# DoorchimeCR2B.net
KiCad netlist of a schematic drawn in EAGLE
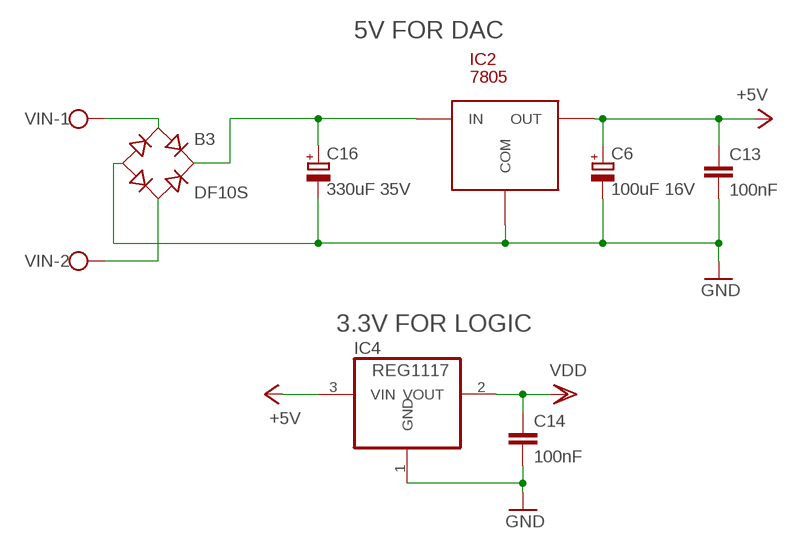
[diagram p0: schematic, sheet 1]
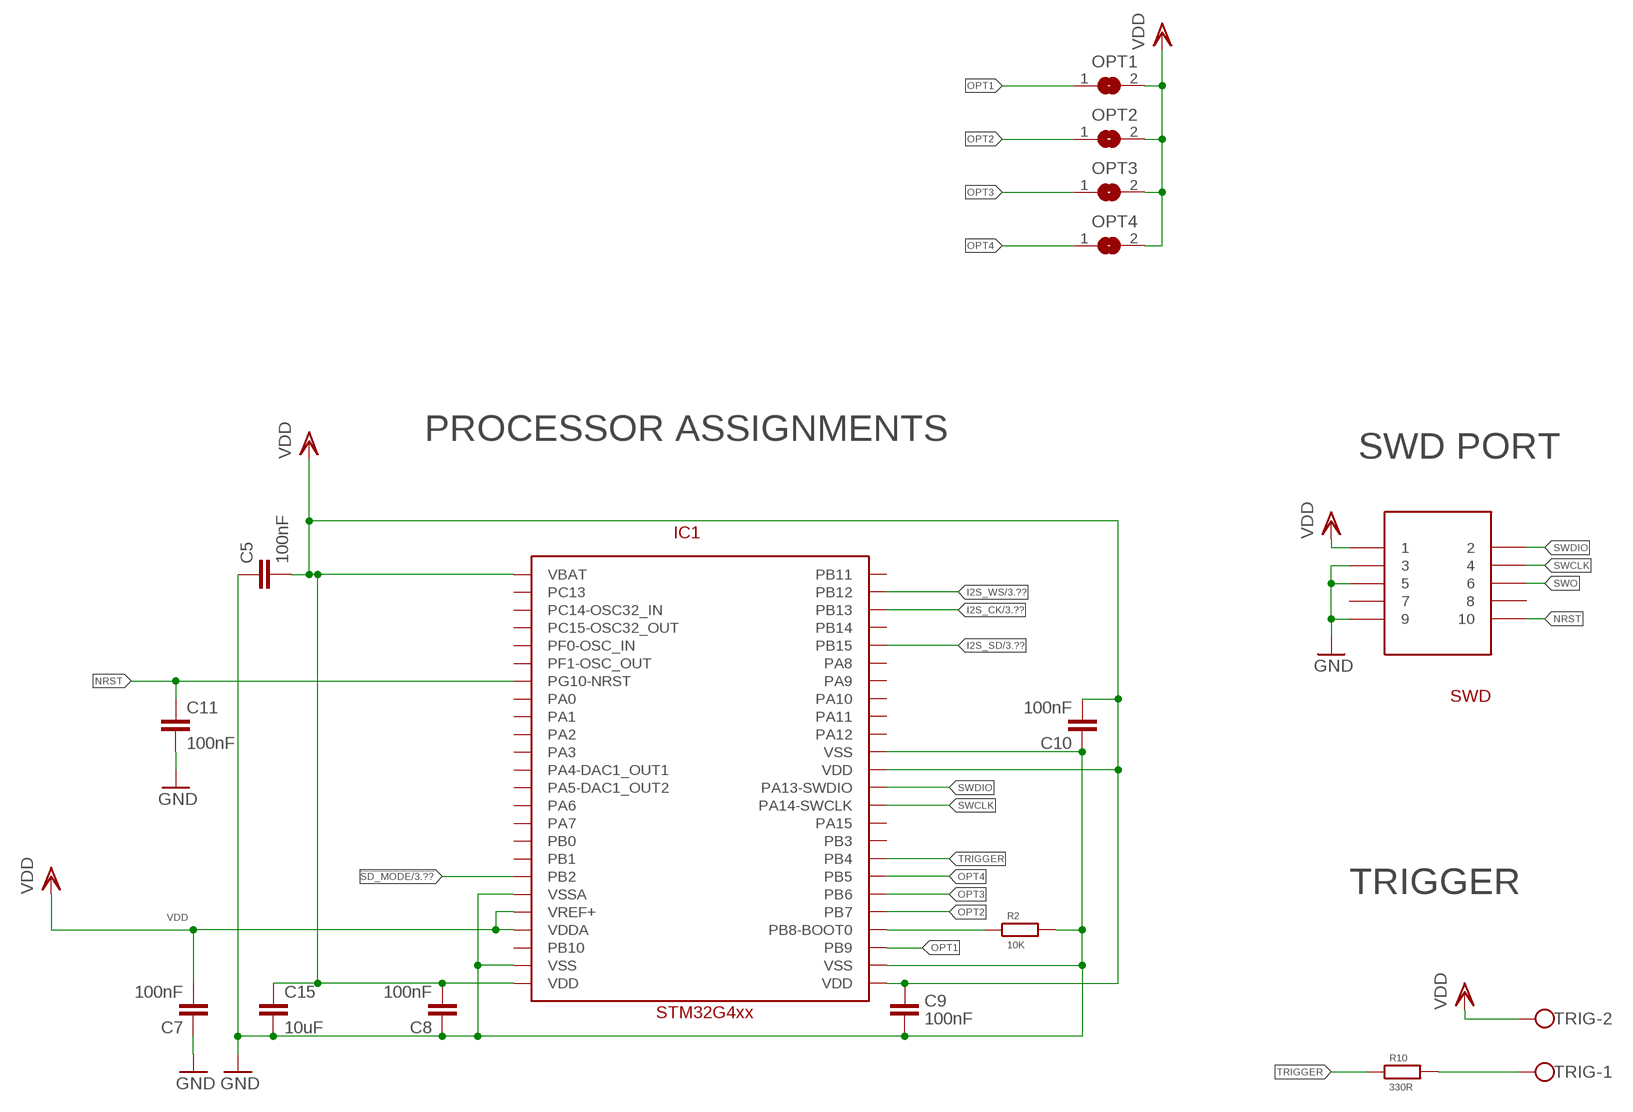
[diagram p1: schematic, sheet 2]
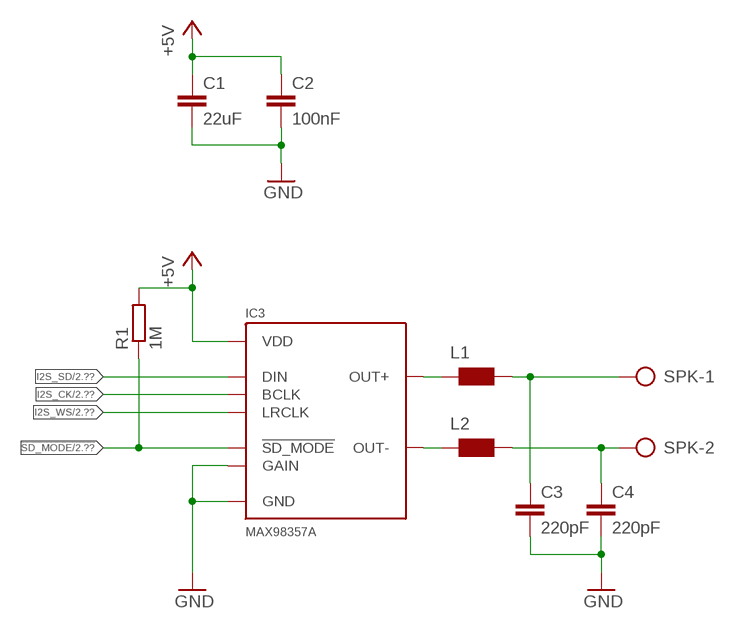
[diagram p2: schematic, sheet 3]

(export (version "E")
  (design (tool "Eeschema 10.0.6"))
  (components
    (comp (ref "B3")
      (value "DF10S")
      (footprint "eagle-import:DFS")
      (libsource (lib "eagle-import") (part "DFS10"))
    )
    (comp (ref "C6")
      (value "100uF 16V")
      (footprint "eagle-import:153CLV-0605")
      (libsource (lib "eagle-import") (part "CPOL-EU153CLV-0605"))
    )
    (comp (ref "C13")
      (value "100nF")
      (footprint "eagle-import:C0603")
      (libsource (lib "eagle-import") (part "C-EUC0603"))
    )
    (comp (ref "C14")
      (value "100nF")
      (footprint "eagle-import:C0603")
      (libsource (lib "eagle-import") (part "C-EUC0603"))
    )
    (comp (ref "C16")
      (value "330uF 35V")
      (footprint "eagle-import:153CLV-0807")
      (libsource (lib "eagle-import") (part "CPOL-EU153CLV-0807"))
    )
    (comp (ref "IC2")
      (value "7805")
      (footprint "eagle-import:D2PAK")
      (libsource (lib "eagle-import") (part "78XX-D2PAK"))
    )
    (comp (ref "IC4")
      (value "REG1117")
      (footprint "eagle-import:SOT223")
      (libsource (lib "eagle-import") (part "REG1117"))
    )
    (comp (ref "VIN")
      (value "W237-102")
      (footprint "eagle-import:W237-102")
      (fields (field (name "MPN") "237-102"))
      (libsource (lib "eagle-import") (part "W237-102"))
    )
    (comp (ref "C1")
      (value "22uF")
      (footprint "eagle-import:C0603")
      (libsource (lib "eagle-import") (part "C-EUC0603"))
    )
    (comp (ref "C2")
      (value "100nF")
      (footprint "eagle-import:C0603")
      (libsource (lib "eagle-import") (part "C-EUC0603"))
    )
    (comp (ref "C3")
      (value "220pF")
      (footprint "eagle-import:C0603")
      (libsource (lib "eagle-import") (part "C-EUC0603"))
    )
    (comp (ref "C4")
      (value "220pF")
      (footprint "eagle-import:C0603")
      (libsource (lib "eagle-import") (part "C-EUC0603"))
    )
    (comp (ref "IC3")
      (value "MAX98357A")
      (footprint "eagle-import:TQFN-16")
      (libsource (lib "eagle-import") (part "MAX98357A"))
    )
    (comp (ref "L1")
      (value "WE-CBF_0603")
      (footprint "eagle-import:0603")
      (libsource (lib "eagle-import") (part "WE-CBF_0603"))
    )
    (comp (ref "L2")
      (value "WE-CBF_0603")
      (footprint "eagle-import:0603")
      (libsource (lib "eagle-import") (part "WE-CBF_0603"))
    )
    (comp (ref "R1")
      (value "1M")
      (footprint "eagle-import:R0603")
      (libsource (lib "eagle-import") (part "R-EU_R0603"))
    )
    (comp (ref "SPK")
      (value "W237-102")
      (footprint "eagle-import:W237-102")
      (fields (field (name "MPN") "237-102"))
      (libsource (lib "eagle-import") (part "W237-102"))
    )
    (comp (ref "C5")
      (value "100nF")
      (footprint "eagle-import:C0603")
      (libsource (lib "eagle-import") (part "C-EUC0603"))
    )
    (comp (ref "C7")
      (value "100nF")
      (footprint "eagle-import:C0603")
      (libsource (lib "eagle-import") (part "C-EUC0603"))
    )
    (comp (ref "C8")
      (value "100nF")
      (footprint "eagle-import:C0603")
      (libsource (lib "eagle-import") (part "C-EUC0603"))
    )
    (comp (ref "C9")
      (value "100nF")
      (footprint "eagle-import:C0603")
      (libsource (lib "eagle-import") (part "C-EUC0603"))
    )
    (comp (ref "C10")
      (value "100nF")
      (footprint "eagle-import:C0603")
      (libsource (lib "eagle-import") (part "C-EUC0603"))
    )
    (comp (ref "C11")
      (value "100nF")
      (footprint "eagle-import:C0603")
      (libsource (lib "eagle-import") (part "C-EUC0603"))
    )
    (comp (ref "C15")
      (value "10uF")
      (footprint "eagle-import:C0603")
      (libsource (lib "eagle-import") (part "C-EUC0603"))
    )
    (comp (ref "IC1")
      (value "STM32G4xx")
      (footprint "eagle-import:TQFP48")
      (libsource (lib "eagle-import") (part "STM32G431-C8T6"))
    )
    (comp (ref "OPT1")
      (value "SJ")
      (footprint "eagle-import:SJ")
      (libsource (lib "eagle-import") (part "SJ"))
    )
    (comp (ref "OPT2")
      (value "SJ")
      (footprint "eagle-import:SJ")
      (libsource (lib "eagle-import") (part "SJ"))
    )
    (comp (ref "OPT3")
      (value "SJ")
      (footprint "eagle-import:SJ")
      (libsource (lib "eagle-import") (part "SJ"))
    )
    (comp (ref "OPT4")
      (value "SJ")
      (footprint "eagle-import:SJ")
      (libsource (lib "eagle-import") (part "SJ"))
    )
    (comp (ref "R2")
      (value "10K")
      (footprint "eagle-import:R0603")
      (libsource (lib "eagle-import") (part "R-EU_R0603"))
    )
    (comp (ref "R10")
      (value "330R")
      (footprint "eagle-import:R0603")
      (libsource (lib "eagle-import") (part "R-EU_R0603"))
    )
    (comp (ref "SWD")
      (value "FTSH-105-01")
      (footprint "eagle-import:FTSH-105-01-XXX-DV-K")
      (libsource (lib "eagle-import") (part "FTSH-105-01"))
    )
    (comp (ref "TRIG")
      (value "W237-102")
      (footprint "eagle-import:W237-102")
      (fields (field (name "MPN") "237-102"))
      (libsource (lib "eagle-import") (part "W237-102"))
    )
  )
  (nets
    (net (code "1") (name "+5V") (class "Default")
      (node (ref "C1") (pin "1") (pinfunction "1_1") (pintype "passive"))
      (node (ref "C13") (pin "1") (pinfunction "1_1") (pintype "passive"))
      (node (ref "C2") (pin "1") (pinfunction "1_1") (pintype "passive"))
      (node (ref "C6") (pin "+") (pinfunction "+_+") (pintype "passive"))
      (node (ref "IC2") (pin "OUT") (pinfunction "OUT_OUT") (pintype "bidirectional"))
      (node (ref "IC3") (pin "P$7") (pinfunction "VDD_P$7") (pintype "bidirectional"))
      (node (ref "IC3") (pin "P$8") (pinfunction "VDD_P$8") (pintype "bidirectional"))
      (node (ref "IC4") (pin "3") (pinfunction "VIN_3") (pintype "input"))
      (node (ref "R1") (pin "2") (pinfunction "2_2") (pintype "passive"))
    )
    (net (code "2") (name "GND") (class "Default")
      (node (ref "B3") (pin "-") (pinfunction "-_-") (pintype "passive"))
      (node (ref "C1") (pin "2") (pinfunction "2_2") (pintype "passive"))
      (node (ref "C10") (pin "1") (pinfunction "1_1") (pintype "passive"))
      (node (ref "C11") (pin "2") (pinfunction "2_2") (pintype "passive"))
      (node (ref "C13") (pin "2") (pinfunction "2_2") (pintype "passive"))
      (node (ref "C14") (pin "2") (pinfunction "2_2") (pintype "passive"))
      (node (ref "C15") (pin "2") (pinfunction "2_2") (pintype "passive"))
      (node (ref "C16") (pin "-") (pinfunction "-_-") (pintype "passive"))
      (node (ref "C2") (pin "2") (pinfunction "2_2") (pintype "passive"))
      (node (ref "C3") (pin "2") (pinfunction "2_2") (pintype "passive"))
      (node (ref "C4") (pin "2") (pinfunction "2_2") (pintype "passive"))
      (node (ref "C5") (pin "1") (pinfunction "1_1") (pintype "passive"))
      (node (ref "C6") (pin "-") (pinfunction "-_-") (pintype "passive"))
      (node (ref "C7") (pin "1") (pinfunction "1_1") (pintype "passive"))
      (node (ref "C8") (pin "1") (pinfunction "1_1") (pintype "passive"))
      (node (ref "C9") (pin "1") (pinfunction "1_1") (pintype "passive"))
      (node (ref "IC1") (pin "VSS@23") (pinfunction "VSS_VSS@23") (pintype "power_in"))
      (node (ref "IC1") (pin "VSS@35") (pinfunction "VSS_VSS@35") (pintype "power_in"))
      (node (ref "IC1") (pin "VSS@47") (pinfunction "VSS_VSS@47") (pintype "power_in"))
      (node (ref "IC1") (pin "VSSA") (pinfunction "VSSA_VSSA") (pintype "power_in"))
      (node (ref "IC2") (pin "COM") (pinfunction "COM_COM") (pintype "bidirectional"))
      (node (ref "IC3") (pin "P$11") (pinfunction "GND_P$11") (pintype "bidirectional"))
      (node (ref "IC3") (pin "P$15") (pinfunction "GND_P$15") (pintype "bidirectional"))
      (node (ref "IC3") (pin "P$2") (pinfunction "GAIN_P$2") (pintype "bidirectional"))
      (node (ref "IC3") (pin "P$3") (pinfunction "GND_P$3") (pintype "bidirectional"))
      (node (ref "IC3") (pin "P$EP") (pinfunction "GND_P$EP") (pintype "bidirectional"))
      (node (ref "IC4") (pin "1") (pinfunction "GND_1") (pintype "power_in"))
      (node (ref "R2") (pin "2") (pinfunction "2_2") (pintype "passive"))
      (node (ref "SWD") (pin "3") (pinfunction "3_3") (pintype "passive"))
      (node (ref "SWD") (pin "5") (pinfunction "5_5") (pintype "passive"))
      (node (ref "SWD") (pin "9") (pinfunction "9_9") (pintype "passive"))
    )
    (net (code "3") (name "I2S_CK") (class "Default")
      (node (ref "IC1") (pin "PB13") (pinfunction "PB13_PB13") (pintype "bidirectional"))
      (node (ref "IC3") (pin "P$16") (pinfunction "BCLK_P$16") (pintype "bidirectional"))
    )
    (net (code "4") (name "I2S_SD") (class "Default")
      (node (ref "IC1") (pin "PB15") (pinfunction "PB15_PB15") (pintype "bidirectional"))
      (node (ref "IC3") (pin "P$1") (pinfunction "DIN_P$1") (pintype "bidirectional"))
    )
    (net (code "5") (name "I2S_WS") (class "Default")
      (node (ref "IC1") (pin "PB12") (pinfunction "PB12_PB12") (pintype "bidirectional"))
      (node (ref "IC3") (pin "P$14") (pinfunction "LRCLK_P$14") (pintype "bidirectional"))
    )
    (net (code "6") (name "NRST") (class "Default")
      (node (ref "C11") (pin "1") (pinfunction "1_1") (pintype "passive"))
      (node (ref "IC1") (pin "PG10-NRST") (pinfunction "PG10-NRST_PG10-NRST") (pintype "bidirectional"))
      (node (ref "SWD") (pin "10") (pinfunction "10_10") (pintype "passive"))
    )
    (net (code "7") (name "Net-(B3-Pad+)") (class "Default")
      (node (ref "B3") (pin "+") (pinfunction "+_+") (pintype "passive"))
      (node (ref "C16") (pin "+") (pinfunction "+_+") (pintype "passive"))
      (node (ref "IC2") (pin "IN") (pinfunction "IN_IN") (pintype "bidirectional"))
    )
    (net (code "8") (name "Net-(IC1-PadPB8-BOOT0)") (class "Default")
      (node (ref "IC1") (pin "PB8-BOOT0") (pinfunction "PB8-BOOT0_PB8-BOOT0") (pintype "bidirectional"))
      (node (ref "R2") (pin "1") (pinfunction "1_1") (pintype "passive"))
    )
    (net (code "9") (name "Net-(IC3-OUT+)") (class "Default")
      (node (ref "IC3") (pin "P$9") (pinfunction "OUT+_P$9") (pintype "bidirectional"))
      (node (ref "L1") (pin "1") (pinfunction "1_1") (pintype "passive"))
    )
    (net (code "10") (name "Net-(IC3-OUT-)") (class "Default")
      (node (ref "IC3") (pin "P$10") (pinfunction "OUT-_P$10") (pintype "bidirectional"))
      (node (ref "L2") (pin "1") (pinfunction "1_1") (pintype "passive"))
    )
    (net (code "11") (name "Net-(SPKA-KL)") (class "Default")
      (node (ref "C3") (pin "1") (pinfunction "1_1") (pintype "passive"))
      (node (ref "L1") (pin "2") (pinfunction "2_2") (pintype "passive"))
      (node (ref "SPK") (pin "1") (pinfunction "KL_1") (pintype "passive"))
    )
    (net (code "12") (name "Net-(SPKB-KL)") (class "Default")
      (node (ref "C4") (pin "1") (pinfunction "1_1") (pintype "passive"))
      (node (ref "L2") (pin "2") (pinfunction "2_2") (pintype "passive"))
      (node (ref "SPK") (pin "2") (pinfunction "KL_2") (pintype "passive"))
    )
    (net (code "13") (name "Net-(TRIGA-KL)") (class "Default")
      (node (ref "R10") (pin "2") (pinfunction "2_2") (pintype "passive"))
      (node (ref "TRIG") (pin "1") (pinfunction "KL_1") (pintype "passive"))
    )
    (net (code "14") (name "Net-(VINA-KL)") (class "Default")
      (node (ref "B3") (pin "AC1") (pinfunction "AC1_AC1") (pintype "passive"))
      (node (ref "VIN") (pin "1") (pinfunction "KL_1") (pintype "passive"))
    )
    (net (code "15") (name "Net-(VINB-KL)") (class "Default")
      (node (ref "B3") (pin "AC2") (pinfunction "AC2_AC2") (pintype "passive"))
      (node (ref "VIN") (pin "2") (pinfunction "KL_2") (pintype "passive"))
    )
    (net (code "16") (name "OPT1") (class "Default")
      (node (ref "IC1") (pin "PB9") (pinfunction "PB9_PB9") (pintype "bidirectional"))
      (node (ref "OPT1") (pin "1") (pinfunction "1_1") (pintype "passive"))
    )
    (net (code "17") (name "OPT2") (class "Default")
      (node (ref "IC1") (pin "PB7") (pinfunction "PB7_PB7") (pintype "bidirectional"))
      (node (ref "OPT2") (pin "1") (pinfunction "1_1") (pintype "passive"))
    )
    (net (code "18") (name "OPT3") (class "Default")
      (node (ref "IC1") (pin "PB6") (pinfunction "PB6_PB6") (pintype "bidirectional"))
      (node (ref "OPT3") (pin "1") (pinfunction "1_1") (pintype "passive"))
    )
    (net (code "19") (name "OPT4") (class "Default")
      (node (ref "IC1") (pin "PB5") (pinfunction "PB5_PB5") (pintype "bidirectional"))
      (node (ref "OPT4") (pin "1") (pinfunction "1_1") (pintype "passive"))
    )
    (net (code "20") (name "SWCLK") (class "Default")
      (node (ref "IC1") (pin "PA14-SWCLK") (pinfunction "PA14-SWCLK_PA14-SWCLK") (pintype "bidirectional"))
      (node (ref "SWD") (pin "4") (pinfunction "4_4") (pintype "passive"))
    )
    (net (code "21") (name "SWDIO") (class "Default")
      (node (ref "IC1") (pin "PA13-SWDIO") (pinfunction "PA13-SWDIO_PA13-SWDIO") (pintype "bidirectional"))
      (node (ref "SWD") (pin "2") (pinfunction "2_2") (pintype "passive"))
    )
    (net (code "22") (name "SWO") (class "Default")
      (node (ref "SWD") (pin "6") (pinfunction "6_6") (pintype "passive"))
    )
    (net (code "23") (name "TRIGGER") (class "Default")
      (node (ref "IC1") (pin "PB4") (pinfunction "PB4_PB4") (pintype "bidirectional"))
      (node (ref "R10") (pin "1") (pinfunction "1_1") (pintype "passive"))
    )
    (net (code "24") (name "VDD") (class "Default")
      (node (ref "C10") (pin "2") (pinfunction "2_2") (pintype "passive"))
      (node (ref "C14") (pin "1") (pinfunction "1_1") (pintype "passive"))
      (node (ref "C15") (pin "1") (pinfunction "1_1") (pintype "passive"))
      (node (ref "C5") (pin "2") (pinfunction "2_2") (pintype "passive"))
      (node (ref "C7") (pin "2") (pinfunction "2_2") (pintype "passive"))
      (node (ref "C8") (pin "2") (pinfunction "2_2") (pintype "passive"))
      (node (ref "C9") (pin "2") (pinfunction "2_2") (pintype "passive"))
      (node (ref "IC1") (pin "VBAT") (pinfunction "VBAT_VBAT") (pintype "power_in"))
      (node (ref "IC1") (pin "VDD@24") (pinfunction "VDD_VDD@24") (pintype "power_in"))
      (node (ref "IC1") (pin "VDD@36") (pinfunction "VDD_VDD@36") (pintype "power_in"))
      (node (ref "IC1") (pin "VDD@48") (pinfunction "VDD_VDD@48") (pintype "power_in"))
      (node (ref "IC1") (pin "VDDA") (pinfunction "VDDA_VDDA") (pintype "power_in"))
      (node (ref "IC1") (pin "VREF+") (pinfunction "VREF+_VREF+") (pintype "power_in"))
      (node (ref "IC4") (pin "2") (pinfunction "VOUT_2") (pintype "output"))
      (node (ref "OPT1") (pin "2") (pinfunction "2_2") (pintype "passive"))
      (node (ref "OPT2") (pin "2") (pinfunction "2_2") (pintype "passive"))
      (node (ref "OPT3") (pin "2") (pinfunction "2_2") (pintype "passive"))
      (node (ref "OPT4") (pin "2") (pinfunction "2_2") (pintype "passive"))
      (node (ref "SWD") (pin "1") (pinfunction "1_1") (pintype "passive"))
      (node (ref "TRIG") (pin "2") (pinfunction "KL_2") (pintype "passive"))
    )
    (net (code "25") (name "unconnected-(IC1-PadPA0)") (class "Default")
      (node (ref "IC1") (pin "PA0") (pinfunction "PA0_PA0") (pintype "bidirectional"))
    )
    (net (code "26") (name "unconnected-(IC1-PadPA1)") (class "Default")
      (node (ref "IC1") (pin "PA1") (pinfunction "PA1_PA1") (pintype "bidirectional"))
    )
    (net (code "27") (name "unconnected-(IC1-PadPA2)") (class "Default")
      (node (ref "IC1") (pin "PA2") (pinfunction "PA2_PA2") (pintype "bidirectional"))
    )
    (net (code "28") (name "unconnected-(IC1-PadPA3)") (class "Default")
      (node (ref "IC1") (pin "PA3") (pinfunction "PA3_PA3") (pintype "bidirectional"))
    )
    (net (code "29") (name "unconnected-(IC1-PadPA4-DAC1_OUT1)") (class "Default")
      (node (ref "IC1") (pin "PA4-DAC1_OUT1") (pinfunction "PA4-DAC1_OUT1_PA4-DAC1_OUT1") (pintype "bidirectional"))
    )
    (net (code "30") (name "unconnected-(IC1-PadPA5-DAC1_OUT2)") (class "Default")
      (node (ref "IC1") (pin "PA5-DAC1_OUT2") (pinfunction "PA5-DAC1_OUT2_PA5-DAC1_OUT2") (pintype "bidirectional"))
    )
    (net (code "31") (name "unconnected-(IC1-PadPA6)") (class "Default")
      (node (ref "IC1") (pin "PA6") (pinfunction "PA6_PA6") (pintype "bidirectional"))
    )
    (net (code "32") (name "unconnected-(IC1-PadPA7)") (class "Default")
      (node (ref "IC1") (pin "PA7") (pinfunction "PA7_PA7") (pintype "bidirectional"))
    )
    (net (code "33") (name "unconnected-(IC1-PadPA8)") (class "Default")
      (node (ref "IC1") (pin "PA8") (pinfunction "PA8_PA8") (pintype "bidirectional"))
    )
    (net (code "34") (name "unconnected-(IC1-PadPA9)") (class "Default")
      (node (ref "IC1") (pin "PA9") (pinfunction "PA9_PA9") (pintype "bidirectional"))
    )
    (net (code "35") (name "unconnected-(IC1-PadPA10)") (class "Default")
      (node (ref "IC1") (pin "PA10") (pinfunction "PA10_PA10") (pintype "bidirectional"))
    )
    (net (code "36") (name "unconnected-(IC1-PadPA11)") (class "Default")
      (node (ref "IC1") (pin "PA11") (pinfunction "PA11_PA11") (pintype "bidirectional"))
    )
    (net (code "37") (name "unconnected-(IC1-PadPA12)") (class "Default")
      (node (ref "IC1") (pin "PA12") (pinfunction "PA12_PA12") (pintype "bidirectional"))
    )
    (net (code "38") (name "unconnected-(IC1-PadPA15)") (class "Default")
      (node (ref "IC1") (pin "PA15") (pinfunction "PA15_PA15") (pintype "bidirectional"))
    )
    (net (code "39") (name "unconnected-(IC1-PadPB0)") (class "Default")
      (node (ref "IC1") (pin "PB0") (pinfunction "PB0_PB0") (pintype "bidirectional"))
    )
    (net (code "40") (name "unconnected-(IC1-PadPB1)") (class "Default")
      (node (ref "IC1") (pin "PB1") (pinfunction "PB1_PB1") (pintype "bidirectional"))
    )
    (net (code "41") (name "unconnected-(IC1-PadPB3)") (class "Default")
      (node (ref "IC1") (pin "PB3") (pinfunction "PB3_PB3") (pintype "bidirectional"))
    )
    (net (code "42") (name "unconnected-(IC1-PadPB10)") (class "Default")
      (node (ref "IC1") (pin "PB10") (pinfunction "PB10_PB10") (pintype "bidirectional"))
    )
    (net (code "43") (name "unconnected-(IC1-PadPB11)") (class "Default")
      (node (ref "IC1") (pin "PB11") (pinfunction "PB11_PB11") (pintype "bidirectional"))
    )
    (net (code "44") (name "unconnected-(IC1-PadPB14)") (class "Default")
      (node (ref "IC1") (pin "PB14") (pinfunction "PB14_PB14") (pintype "bidirectional"))
    )
    (net (code "45") (name "unconnected-(IC1-PadPC13)") (class "Default")
      (node (ref "IC1") (pin "PC13") (pinfunction "PC13_PC13") (pintype "bidirectional"))
    )
    (net (code "46") (name "unconnected-(IC1-PadPC14-OSC32_IN)") (class "Default")
      (node (ref "IC1") (pin "PC14-OSC32_IN") (pinfunction "PC14-OSC32_IN_PC14-OSC32_IN") (pintype "bidirectional"))
    )
    (net (code "47") (name "unconnected-(IC1-PadPC15-OSC32_OUT)") (class "Default")
      (node (ref "IC1") (pin "PC15-OSC32_OUT") (pinfunction "PC15-OSC32_OUT_PC15-OSC32_OUT") (pintype "bidirectional"))
    )
    (net (code "48") (name "unconnected-(IC1-PadPF0-OSC_IN)") (class "Default")
      (node (ref "IC1") (pin "PF0-OSC_IN") (pinfunction "PF0-OSC_IN_PF0-OSC_IN") (pintype "bidirectional"))
    )
    (net (code "49") (name "unconnected-(IC1-PadPF1-OSC_OUT)") (class "Default")
      (node (ref "IC1") (pin "PF1-OSC_OUT") (pinfunction "PF1-OSC_OUT_PF1-OSC_OUT") (pintype "bidirectional"))
    )
    (net (code "50") (name "unconnected-(SWD-Pad7)") (class "Default")
      (node (ref "SWD") (pin "7") (pinfunction "7_7") (pintype "passive"))
    )
    (net (code "51") (name "unconnected-(SWD-Pad8)") (class "Default")
      (node (ref "SWD") (pin "8") (pinfunction "8_8") (pintype "passive"))
    )
    (net (code "52") (name "~{SD_MODE}") (class "Default")
      (node (ref "IC1") (pin "PB2") (pinfunction "PB2_PB2") (pintype "bidirectional"))
      (node (ref "IC3") (pin "P$4") (pinfunction "~{SD_MODE}_P$4") (pintype "bidirectional"))
      (node (ref "R1") (pin "1") (pinfunction "1_1") (pintype "passive"))
    )
  )
)
